# esp32-poe-thermocouple-hat-prod-onboard.net
KiCad netlist of a schematic drawn in EAGLE
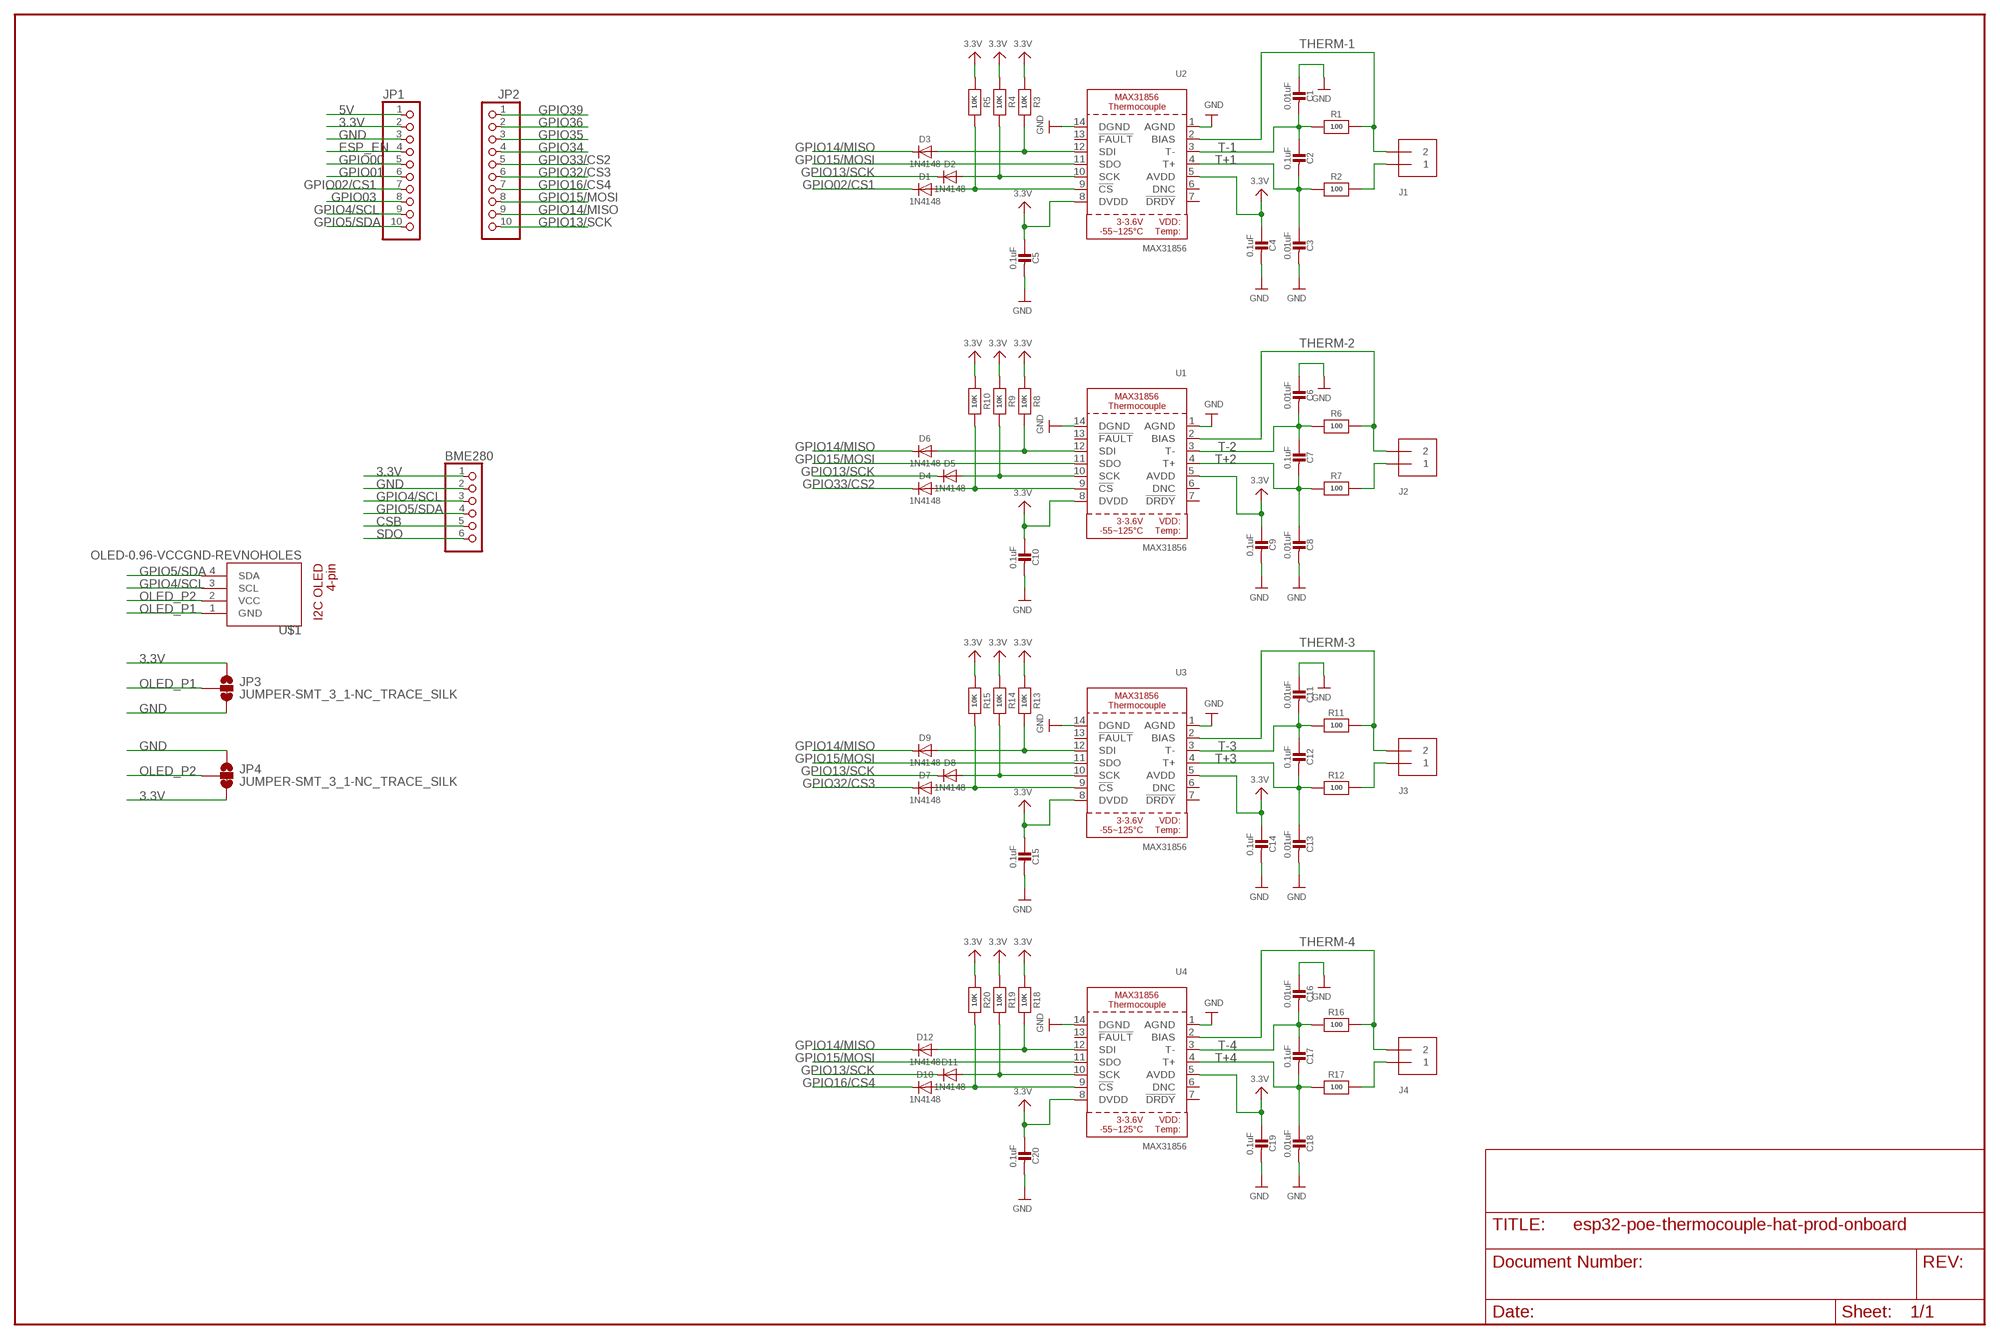
[diagram p0: schematic, sheet 1]

(export (version "E")
  (design (tool "Eeschema 10.0.6"))
  (components
    (comp (ref "BME280")
      (value "PINHD-1X6")
      (footprint "eagle-import:1X06")
      (libsource (lib "eagle-import") (part "PINHD-1X6"))
    )
    (comp (ref "C1")
      (value "0.01uF")
      (footprint "eagle-import:0805_10MGAP")
      (libsource (lib "eagle-import") (part "CAP_CERAMIC0805_10MGAP"))
    )
    (comp (ref "C2")
      (value "0.1uF")
      (footprint "eagle-import:0805-NO")
      (libsource (lib "eagle-import") (part "CAP_CERAMIC0805-NOOUTLINE"))
    )
    (comp (ref "C3")
      (value "0.01uF")
      (footprint "eagle-import:0805-NO")
      (libsource (lib "eagle-import") (part "CAP_CERAMIC0805-NOOUTLINE"))
    )
    (comp (ref "C4")
      (value "0.1uF")
      (footprint "eagle-import:0805-NO")
      (libsource (lib "eagle-import") (part "CAP_CERAMIC0805-NOOUTLINE"))
    )
    (comp (ref "C5")
      (value "0.1uF")
      (footprint "eagle-import:0805-NO")
      (libsource (lib "eagle-import") (part "CAP_CERAMIC0805-NOOUTLINE"))
    )
    (comp (ref "C6")
      (value "0.01uF")
      (footprint "eagle-import:0805_10MGAP")
      (libsource (lib "eagle-import") (part "CAP_CERAMIC0805_10MGAP"))
    )
    (comp (ref "C7")
      (value "0.1uF")
      (footprint "eagle-import:0805-NO")
      (libsource (lib "eagle-import") (part "CAP_CERAMIC0805-NOOUTLINE"))
    )
    (comp (ref "C8")
      (value "0.01uF")
      (footprint "eagle-import:0805-NO")
      (libsource (lib "eagle-import") (part "CAP_CERAMIC0805-NOOUTLINE"))
    )
    (comp (ref "C9")
      (value "0.1uF")
      (footprint "eagle-import:0805-NO")
      (libsource (lib "eagle-import") (part "CAP_CERAMIC0805-NOOUTLINE"))
    )
    (comp (ref "C10")
      (value "0.1uF")
      (footprint "eagle-import:0805-NO")
      (libsource (lib "eagle-import") (part "CAP_CERAMIC0805-NOOUTLINE"))
    )
    (comp (ref "C11")
      (value "0.01uF")
      (footprint "eagle-import:0805_10MGAP")
      (libsource (lib "eagle-import") (part "CAP_CERAMIC0805_10MGAP"))
    )
    (comp (ref "C12")
      (value "0.1uF")
      (footprint "eagle-import:0805-NO")
      (libsource (lib "eagle-import") (part "CAP_CERAMIC0805-NOOUTLINE"))
    )
    (comp (ref "C13")
      (value "0.01uF")
      (footprint "eagle-import:0805-NO")
      (libsource (lib "eagle-import") (part "CAP_CERAMIC0805-NOOUTLINE"))
    )
    (comp (ref "C14")
      (value "0.1uF")
      (footprint "eagle-import:0805-NO")
      (libsource (lib "eagle-import") (part "CAP_CERAMIC0805-NOOUTLINE"))
    )
    (comp (ref "C15")
      (value "0.1uF")
      (footprint "eagle-import:0805-NO")
      (libsource (lib "eagle-import") (part "CAP_CERAMIC0805-NOOUTLINE"))
    )
    (comp (ref "C16")
      (value "0.01uF")
      (footprint "eagle-import:0805_10MGAP")
      (libsource (lib "eagle-import") (part "CAP_CERAMIC0805_10MGAP"))
    )
    (comp (ref "C17")
      (value "0.1uF")
      (footprint "eagle-import:0805-NO")
      (libsource (lib "eagle-import") (part "CAP_CERAMIC0805-NOOUTLINE"))
    )
    (comp (ref "C18")
      (value "0.01uF")
      (footprint "eagle-import:0805-NO")
      (libsource (lib "eagle-import") (part "CAP_CERAMIC0805-NOOUTLINE"))
    )
    (comp (ref "C19")
      (value "0.1uF")
      (footprint "eagle-import:0805-NO")
      (libsource (lib "eagle-import") (part "CAP_CERAMIC0805-NOOUTLINE"))
    )
    (comp (ref "C20")
      (value "0.1uF")
      (footprint "eagle-import:0805-NO")
      (libsource (lib "eagle-import") (part "CAP_CERAMIC0805-NOOUTLINE"))
    )
    (comp (ref "D1")
      (value "1N4148")
      (footprint "eagle-import:SOD-323")
      (libsource (lib "eagle-import") (part "DIODESOD-323"))
    )
    (comp (ref "D2")
      (value "1N4148")
      (footprint "eagle-import:SOD-323")
      (libsource (lib "eagle-import") (part "DIODESOD-323"))
    )
    (comp (ref "D3")
      (value "1N4148")
      (footprint "eagle-import:SOD-323")
      (libsource (lib "eagle-import") (part "DIODESOD-323"))
    )
    (comp (ref "D4")
      (value "1N4148")
      (footprint "eagle-import:SOD-323")
      (libsource (lib "eagle-import") (part "DIODESOD-323"))
    )
    (comp (ref "D5")
      (value "1N4148")
      (footprint "eagle-import:SOD-323")
      (libsource (lib "eagle-import") (part "DIODESOD-323"))
    )
    (comp (ref "D6")
      (value "1N4148")
      (footprint "eagle-import:SOD-323")
      (libsource (lib "eagle-import") (part "DIODESOD-323"))
    )
    (comp (ref "D7")
      (value "1N4148")
      (footprint "eagle-import:SOD-323")
      (libsource (lib "eagle-import") (part "DIODESOD-323"))
    )
    (comp (ref "D8")
      (value "1N4148")
      (footprint "eagle-import:SOD-323")
      (libsource (lib "eagle-import") (part "DIODESOD-323"))
    )
    (comp (ref "D9")
      (value "1N4148")
      (footprint "eagle-import:SOD-323")
      (libsource (lib "eagle-import") (part "DIODESOD-323"))
    )
    (comp (ref "D10")
      (value "1N4148")
      (footprint "eagle-import:SOD-323")
      (libsource (lib "eagle-import") (part "DIODESOD-323"))
    )
    (comp (ref "D11")
      (value "1N4148")
      (footprint "eagle-import:SOD-323")
      (libsource (lib "eagle-import") (part "DIODESOD-323"))
    )
    (comp (ref "D12")
      (value "1N4148")
      (footprint "eagle-import:SOD-323")
      (libsource (lib "eagle-import") (part "DIODESOD-323"))
    )
    (comp (ref "J1")
      (value "TERMBLOCK_1X2-7.62-SCREW")
      (footprint "eagle-import:TERMBLOCK_1X2-7.62MM-SCREW")
      (libsource (lib "eagle-import") (part "TERMBLOCK_1X2-7.62-SCREW"))
    )
    (comp (ref "J2")
      (value "TERMBLOCK_1X2-7.62-SCREW")
      (footprint "eagle-import:TERMBLOCK_1X2-7.62MM-SCREW")
      (libsource (lib "eagle-import") (part "TERMBLOCK_1X2-7.62-SCREW"))
    )
    (comp (ref "J3")
      (value "TERMBLOCK_1X2-7.62-SCREW")
      (footprint "eagle-import:TERMBLOCK_1X2-7.62MM-SCREW")
      (libsource (lib "eagle-import") (part "TERMBLOCK_1X2-7.62-SCREW"))
    )
    (comp (ref "J4")
      (value "TERMBLOCK_1X2-7.62-SCREW")
      (footprint "eagle-import:TERMBLOCK_1X2-7.62MM-SCREW")
      (libsource (lib "eagle-import") (part "TERMBLOCK_1X2-7.62-SCREW"))
    )
    (comp (ref "JP1")
      (value "PINHD-1X10")
      (footprint "eagle-import:1X10")
      (libsource (lib "eagle-import") (part "PINHD-1X10"))
    )
    (comp (ref "JP2")
      (value "PINHD-1X10")
      (footprint "eagle-import:1X10")
      (libsource (lib "eagle-import") (part "PINHD-1X10"))
    )
    (comp (ref "JP3")
      (value "JUMPER-SMT_3_1-NC_TRACE_SILK")
      (footprint "eagle-import:SMT-JUMPER_3_1-NC_TRACE_SILK")
      (libsource (lib "eagle-import") (part "JUMPER-SMT_3_1-NC_TRACE_SILK"))
    )
    (comp (ref "JP4")
      (value "JUMPER-SMT_3_1-NC_TRACE_SILK")
      (footprint "eagle-import:SMT-JUMPER_3_1-NC_TRACE_SILK")
      (libsource (lib "eagle-import") (part "JUMPER-SMT_3_1-NC_TRACE_SILK"))
    )
    (comp (ref "R1")
      (value "100")
      (footprint "eagle-import:0805-NO")
      (libsource (lib "eagle-import") (part "RESISTOR0805_NOOUTLINE"))
    )
    (comp (ref "R2")
      (value "100")
      (footprint "eagle-import:0805-NO")
      (libsource (lib "eagle-import") (part "RESISTOR0805_NOOUTLINE"))
    )
    (comp (ref "R3")
      (value "10K")
      (footprint "eagle-import:0805-NO")
      (libsource (lib "eagle-import") (part "RESISTOR0805_NOOUTLINE"))
    )
    (comp (ref "R4")
      (value "10K")
      (footprint "eagle-import:0805-NO")
      (libsource (lib "eagle-import") (part "RESISTOR0805_NOOUTLINE"))
    )
    (comp (ref "R5")
      (value "10K")
      (footprint "eagle-import:0805-NO")
      (libsource (lib "eagle-import") (part "RESISTOR0805_NOOUTLINE"))
    )
    (comp (ref "R6")
      (value "100")
      (footprint "eagle-import:0805-NO")
      (libsource (lib "eagle-import") (part "RESISTOR0805_NOOUTLINE"))
    )
    (comp (ref "R7")
      (value "100")
      (footprint "eagle-import:0805-NO")
      (libsource (lib "eagle-import") (part "RESISTOR0805_NOOUTLINE"))
    )
    (comp (ref "R8")
      (value "10K")
      (footprint "eagle-import:0805-NO")
      (libsource (lib "eagle-import") (part "RESISTOR0805_NOOUTLINE"))
    )
    (comp (ref "R9")
      (value "10K")
      (footprint "eagle-import:0805-NO")
      (libsource (lib "eagle-import") (part "RESISTOR0805_NOOUTLINE"))
    )
    (comp (ref "R10")
      (value "10K")
      (footprint "eagle-import:0805-NO")
      (libsource (lib "eagle-import") (part "RESISTOR0805_NOOUTLINE"))
    )
    (comp (ref "R11")
      (value "100")
      (footprint "eagle-import:0805-NO")
      (libsource (lib "eagle-import") (part "RESISTOR0805_NOOUTLINE"))
    )
    (comp (ref "R12")
      (value "100")
      (footprint "eagle-import:0805-NO")
      (libsource (lib "eagle-import") (part "RESISTOR0805_NOOUTLINE"))
    )
    (comp (ref "R13")
      (value "10K")
      (footprint "eagle-import:0805-NO")
      (libsource (lib "eagle-import") (part "RESISTOR0805_NOOUTLINE"))
    )
    (comp (ref "R14")
      (value "10K")
      (footprint "eagle-import:0805-NO")
      (libsource (lib "eagle-import") (part "RESISTOR0805_NOOUTLINE"))
    )
    (comp (ref "R15")
      (value "10K")
      (footprint "eagle-import:0805-NO")
      (libsource (lib "eagle-import") (part "RESISTOR0805_NOOUTLINE"))
    )
    (comp (ref "R16")
      (value "100")
      (footprint "eagle-import:0805-NO")
      (libsource (lib "eagle-import") (part "RESISTOR0805_NOOUTLINE"))
    )
    (comp (ref "R17")
      (value "100")
      (footprint "eagle-import:0805-NO")
      (libsource (lib "eagle-import") (part "RESISTOR0805_NOOUTLINE"))
    )
    (comp (ref "R18")
      (value "10K")
      (footprint "eagle-import:0805-NO")
      (libsource (lib "eagle-import") (part "RESISTOR0805_NOOUTLINE"))
    )
    (comp (ref "R19")
      (value "10K")
      (footprint "eagle-import:0805-NO")
      (libsource (lib "eagle-import") (part "RESISTOR0805_NOOUTLINE"))
    )
    (comp (ref "R20")
      (value "10K")
      (footprint "eagle-import:0805-NO")
      (libsource (lib "eagle-import") (part "RESISTOR0805_NOOUTLINE"))
    )
    (comp (ref "U$1")
      (value "OLED-0.96-VCCGND-REVNOHOLES")
      (footprint "eagle-import:OLED-I2C-4PIN-NOHOLES")
      (libsource (lib "eagle-import") (part "OLED-0.96-VCCGND-REVNOHOLES"))
    )
    (comp (ref "U1")
      (value "MAX31856")
      (footprint "eagle-import:TSSOP14")
      (libsource (lib "eagle-import") (part "MAX31856"))
    )
    (comp (ref "U2")
      (value "MAX31856")
      (footprint "eagle-import:TSSOP14")
      (libsource (lib "eagle-import") (part "MAX31856"))
    )
    (comp (ref "U3")
      (value "MAX31856")
      (footprint "eagle-import:TSSOP14")
      (libsource (lib "eagle-import") (part "MAX31856"))
    )
    (comp (ref "U4")
      (value "MAX31856")
      (footprint "eagle-import:TSSOP14")
      (libsource (lib "eagle-import") (part "MAX31856"))
    )
  )
  (nets
    (net (code "1") (name "/5V") (class "Default")
      (node (ref "JP1") (pin "1") (pinfunction "1_1") (pintype "passive"))
    )
    (net (code "2") (name "/CSB") (class "Default")
      (node (ref "BME280") (pin "5") (pinfunction "5_5") (pintype "passive"))
    )
    (net (code "3") (name "/ESP_EN") (class "Default")
      (node (ref "JP1") (pin "4") (pinfunction "4_4") (pintype "passive"))
    )
    (net (code "4") (name "/GPIO00") (class "Default")
      (node (ref "JP1") (pin "5") (pinfunction "5_5") (pintype "passive"))
    )
    (net (code "5") (name "/GPIO01") (class "Default")
      (node (ref "JP1") (pin "6") (pinfunction "6_6") (pintype "passive"))
    )
    (net (code "6") (name "/GPIO02{slash}CS1") (class "Default")
      (node (ref "D1") (pin "C") (pinfunction "C_C") (pintype "passive"))
      (node (ref "JP1") (pin "7") (pinfunction "7_7") (pintype "passive"))
    )
    (net (code "7") (name "/GPIO03") (class "Default")
      (node (ref "JP1") (pin "8") (pinfunction "8_8") (pintype "passive"))
    )
    (net (code "8") (name "/GPIO4{slash}SCL") (class "Default")
      (node (ref "BME280") (pin "3") (pinfunction "3_3") (pintype "passive"))
      (node (ref "JP1") (pin "9") (pinfunction "9_9") (pintype "passive"))
      (node (ref "U$1") (pin "3") (pinfunction "SCL_3") (pintype "bidirectional"))
    )
    (net (code "9") (name "/GPIO5{slash}SDA") (class "Default")
      (node (ref "BME280") (pin "4") (pinfunction "4_4") (pintype "passive"))
      (node (ref "JP1") (pin "10") (pinfunction "10_10") (pintype "passive"))
      (node (ref "U$1") (pin "4") (pinfunction "SDA_4") (pintype "bidirectional"))
    )
    (net (code "10") (name "/GPIO13{slash}SCK") (class "Default")
      (node (ref "D11") (pin "C") (pinfunction "C_C") (pintype "passive"))
      (node (ref "D2") (pin "C") (pinfunction "C_C") (pintype "passive"))
      (node (ref "D5") (pin "C") (pinfunction "C_C") (pintype "passive"))
      (node (ref "D8") (pin "C") (pinfunction "C_C") (pintype "passive"))
      (node (ref "JP2") (pin "10") (pinfunction "10_10") (pintype "passive"))
    )
    (net (code "11") (name "/GPIO14{slash}MISO") (class "Default")
      (node (ref "D12") (pin "C") (pinfunction "C_C") (pintype "passive"))
      (node (ref "D3") (pin "C") (pinfunction "C_C") (pintype "passive"))
      (node (ref "D6") (pin "C") (pinfunction "C_C") (pintype "passive"))
      (node (ref "D9") (pin "C") (pinfunction "C_C") (pintype "passive"))
      (node (ref "JP2") (pin "9") (pinfunction "9_9") (pintype "passive"))
    )
    (net (code "12") (name "/GPIO15{slash}MOSI") (class "Default")
      (node (ref "JP2") (pin "8") (pinfunction "8_8") (pintype "passive"))
      (node (ref "U1") (pin "11") (pinfunction "SDO_11") (pintype "output"))
      (node (ref "U2") (pin "11") (pinfunction "SDO_11") (pintype "output"))
      (node (ref "U3") (pin "11") (pinfunction "SDO_11") (pintype "output"))
      (node (ref "U4") (pin "11") (pinfunction "SDO_11") (pintype "output"))
    )
    (net (code "13") (name "/GPIO16{slash}CS4") (class "Default")
      (node (ref "D10") (pin "C") (pinfunction "C_C") (pintype "passive"))
      (node (ref "JP2") (pin "7") (pinfunction "7_7") (pintype "passive"))
    )
    (net (code "14") (name "/GPIO32{slash}CS3") (class "Default")
      (node (ref "D7") (pin "C") (pinfunction "C_C") (pintype "passive"))
      (node (ref "JP2") (pin "6") (pinfunction "6_6") (pintype "passive"))
    )
    (net (code "15") (name "/GPIO33{slash}CS2") (class "Default")
      (node (ref "D4") (pin "C") (pinfunction "C_C") (pintype "passive"))
      (node (ref "JP2") (pin "5") (pinfunction "5_5") (pintype "passive"))
    )
    (net (code "16") (name "/GPIO34") (class "Default")
      (node (ref "JP2") (pin "4") (pinfunction "4_4") (pintype "passive"))
    )
    (net (code "17") (name "/GPIO35") (class "Default")
      (node (ref "JP2") (pin "3") (pinfunction "3_3") (pintype "passive"))
    )
    (net (code "18") (name "/GPIO36") (class "Default")
      (node (ref "JP2") (pin "2") (pinfunction "2_2") (pintype "passive"))
    )
    (net (code "19") (name "/GPIO39") (class "Default")
      (node (ref "JP2") (pin "1") (pinfunction "1_1") (pintype "passive"))
    )
    (net (code "20") (name "/OLED_P1") (class "Default")
      (node (ref "JP3") (pin "2") (pinfunction "2_2") (pintype "passive"))
      (node (ref "U$1") (pin "1") (pinfunction "GND_1") (pintype "bidirectional"))
    )
    (net (code "21") (name "/OLED_P2") (class "Default")
      (node (ref "JP4") (pin "2") (pinfunction "2_2") (pintype "passive"))
      (node (ref "U$1") (pin "2") (pinfunction "VCC_2") (pintype "bidirectional"))
    )
    (net (code "22") (name "/SDO") (class "Default")
      (node (ref "BME280") (pin "6") (pinfunction "6_6") (pintype "passive"))
    )
    (net (code "23") (name "/T+1") (class "Default")
      (node (ref "C2") (pin "2") (pinfunction "2_2") (pintype "passive"))
      (node (ref "C3") (pin "1") (pinfunction "1_1") (pintype "passive"))
      (node (ref "R2") (pin "2") (pinfunction "2_2") (pintype "passive"))
      (node (ref "U2") (pin "4") (pinfunction "T+_4") (pintype "input"))
    )
    (net (code "24") (name "/T+2") (class "Default")
      (node (ref "C7") (pin "2") (pinfunction "2_2") (pintype "passive"))
      (node (ref "C8") (pin "1") (pinfunction "1_1") (pintype "passive"))
      (node (ref "R7") (pin "2") (pinfunction "2_2") (pintype "passive"))
      (node (ref "U1") (pin "4") (pinfunction "T+_4") (pintype "input"))
    )
    (net (code "25") (name "/T+3") (class "Default")
      (node (ref "C12") (pin "2") (pinfunction "2_2") (pintype "passive"))
      (node (ref "C13") (pin "1") (pinfunction "1_1") (pintype "passive"))
      (node (ref "R12") (pin "2") (pinfunction "2_2") (pintype "passive"))
      (node (ref "U3") (pin "4") (pinfunction "T+_4") (pintype "input"))
    )
    (net (code "26") (name "/T+4") (class "Default")
      (node (ref "C17") (pin "2") (pinfunction "2_2") (pintype "passive"))
      (node (ref "C18") (pin "1") (pinfunction "1_1") (pintype "passive"))
      (node (ref "R17") (pin "2") (pinfunction "2_2") (pintype "passive"))
      (node (ref "U4") (pin "4") (pinfunction "T+_4") (pintype "input"))
    )
    (net (code "27") (name "/T-1") (class "Default")
      (node (ref "C1") (pin "2") (pinfunction "2_2") (pintype "passive"))
      (node (ref "C2") (pin "1") (pinfunction "1_1") (pintype "passive"))
      (node (ref "R1") (pin "2") (pinfunction "2_2") (pintype "passive"))
      (node (ref "U2") (pin "3") (pinfunction "T-_3") (pintype "input"))
    )
    (net (code "28") (name "/T-2") (class "Default")
      (node (ref "C6") (pin "2") (pinfunction "2_2") (pintype "passive"))
      (node (ref "C7") (pin "1") (pinfunction "1_1") (pintype "passive"))
      (node (ref "R6") (pin "2") (pinfunction "2_2") (pintype "passive"))
      (node (ref "U1") (pin "3") (pinfunction "T-_3") (pintype "input"))
    )
    (net (code "29") (name "/T-3") (class "Default")
      (node (ref "C11") (pin "2") (pinfunction "2_2") (pintype "passive"))
      (node (ref "C12") (pin "1") (pinfunction "1_1") (pintype "passive"))
      (node (ref "R11") (pin "2") (pinfunction "2_2") (pintype "passive"))
      (node (ref "U3") (pin "3") (pinfunction "T-_3") (pintype "input"))
    )
    (net (code "30") (name "/T-4") (class "Default")
      (node (ref "C16") (pin "2") (pinfunction "2_2") (pintype "passive"))
      (node (ref "C17") (pin "1") (pinfunction "1_1") (pintype "passive"))
      (node (ref "R16") (pin "2") (pinfunction "2_2") (pintype "passive"))
      (node (ref "U4") (pin "3") (pinfunction "T-_3") (pintype "input"))
    )
    (net (code "31") (name "/THERM-1") (class "Default")
      (node (ref "J1") (pin "2") (pinfunction "2_2") (pintype "passive"))
      (node (ref "R1") (pin "1") (pinfunction "1_1") (pintype "passive"))
      (node (ref "U2") (pin "2") (pinfunction "BIAS_2") (pintype "power_in"))
    )
    (net (code "32") (name "/THERM-2") (class "Default")
      (node (ref "J2") (pin "2") (pinfunction "2_2") (pintype "passive"))
      (node (ref "R6") (pin "1") (pinfunction "1_1") (pintype "passive"))
      (node (ref "U1") (pin "2") (pinfunction "BIAS_2") (pintype "power_in"))
    )
    (net (code "33") (name "/THERM-3") (class "Default")
      (node (ref "J3") (pin "2") (pinfunction "2_2") (pintype "passive"))
      (node (ref "R11") (pin "1") (pinfunction "1_1") (pintype "passive"))
      (node (ref "U3") (pin "2") (pinfunction "BIAS_2") (pintype "power_in"))
    )
    (net (code "34") (name "/THERM-4") (class "Default")
      (node (ref "J4") (pin "2") (pinfunction "2_2") (pintype "passive"))
      (node (ref "R16") (pin "1") (pinfunction "1_1") (pintype "passive"))
      (node (ref "U4") (pin "2") (pinfunction "BIAS_2") (pintype "power_in"))
    )
    (net (code "35") (name "3.3V") (class "Default")
      (node (ref "BME280") (pin "1") (pinfunction "1_1") (pintype "passive"))
      (node (ref "C10") (pin "1") (pinfunction "1_1") (pintype "passive"))
      (node (ref "C14") (pin "1") (pinfunction "1_1") (pintype "passive"))
      (node (ref "C15") (pin "1") (pinfunction "1_1") (pintype "passive"))
      (node (ref "C19") (pin "1") (pinfunction "1_1") (pintype "passive"))
      (node (ref "C20") (pin "1") (pinfunction "1_1") (pintype "passive"))
      (node (ref "C4") (pin "1") (pinfunction "1_1") (pintype "passive"))
      (node (ref "C5") (pin "1") (pinfunction "1_1") (pintype "passive"))
      (node (ref "C9") (pin "1") (pinfunction "1_1") (pintype "passive"))
      (node (ref "JP1") (pin "2") (pinfunction "2_2") (pintype "passive"))
      (node (ref "JP3") (pin "1") (pinfunction "1_1") (pintype "passive"))
      (node (ref "JP4") (pin "3") (pinfunction "3_3") (pintype "passive"))
      (node (ref "R10") (pin "2") (pinfunction "2_2") (pintype "passive"))
      (node (ref "R13") (pin "2") (pinfunction "2_2") (pintype "passive"))
      (node (ref "R14") (pin "2") (pinfunction "2_2") (pintype "passive"))
      (node (ref "R15") (pin "2") (pinfunction "2_2") (pintype "passive"))
      (node (ref "R18") (pin "2") (pinfunction "2_2") (pintype "passive"))
      (node (ref "R19") (pin "2") (pinfunction "2_2") (pintype "passive"))
      (node (ref "R20") (pin "2") (pinfunction "2_2") (pintype "passive"))
      (node (ref "R3") (pin "2") (pinfunction "2_2") (pintype "passive"))
      (node (ref "R4") (pin "2") (pinfunction "2_2") (pintype "passive"))
      (node (ref "R5") (pin "2") (pinfunction "2_2") (pintype "passive"))
      (node (ref "R8") (pin "2") (pinfunction "2_2") (pintype "passive"))
      (node (ref "R9") (pin "2") (pinfunction "2_2") (pintype "passive"))
      (node (ref "U1") (pin "5") (pinfunction "AVDD_5") (pintype "power_in"))
      (node (ref "U1") (pin "8") (pinfunction "DVDD_8") (pintype "power_in"))
      (node (ref "U2") (pin "5") (pinfunction "AVDD_5") (pintype "power_in"))
      (node (ref "U2") (pin "8") (pinfunction "DVDD_8") (pintype "power_in"))
      (node (ref "U3") (pin "5") (pinfunction "AVDD_5") (pintype "power_in"))
      (node (ref "U3") (pin "8") (pinfunction "DVDD_8") (pintype "power_in"))
      (node (ref "U4") (pin "5") (pinfunction "AVDD_5") (pintype "power_in"))
      (node (ref "U4") (pin "8") (pinfunction "DVDD_8") (pintype "power_in"))
    )
    (net (code "36") (name "GND") (class "Default")
      (node (ref "BME280") (pin "2") (pinfunction "2_2") (pintype "passive"))
      (node (ref "C1") (pin "1") (pinfunction "1_1") (pintype "passive"))
      (node (ref "C10") (pin "2") (pinfunction "2_2") (pintype "passive"))
      (node (ref "C11") (pin "1") (pinfunction "1_1") (pintype "passive"))
      (node (ref "C13") (pin "2") (pinfunction "2_2") (pintype "passive"))
      (node (ref "C14") (pin "2") (pinfunction "2_2") (pintype "passive"))
      (node (ref "C15") (pin "2") (pinfunction "2_2") (pintype "passive"))
      (node (ref "C16") (pin "1") (pinfunction "1_1") (pintype "passive"))
      (node (ref "C18") (pin "2") (pinfunction "2_2") (pintype "passive"))
      (node (ref "C19") (pin "2") (pinfunction "2_2") (pintype "passive"))
      (node (ref "C20") (pin "2") (pinfunction "2_2") (pintype "passive"))
      (node (ref "C3") (pin "2") (pinfunction "2_2") (pintype "passive"))
      (node (ref "C4") (pin "2") (pinfunction "2_2") (pintype "passive"))
      (node (ref "C5") (pin "2") (pinfunction "2_2") (pintype "passive"))
      (node (ref "C6") (pin "1") (pinfunction "1_1") (pintype "passive"))
      (node (ref "C8") (pin "2") (pinfunction "2_2") (pintype "passive"))
      (node (ref "C9") (pin "2") (pinfunction "2_2") (pintype "passive"))
      (node (ref "JP1") (pin "3") (pinfunction "3_3") (pintype "passive"))
      (node (ref "JP3") (pin "3") (pinfunction "3_3") (pintype "passive"))
      (node (ref "JP4") (pin "1") (pinfunction "1_1") (pintype "passive"))
      (node (ref "U1") (pin "1") (pinfunction "AGND_1") (pintype "power_in"))
      (node (ref "U1") (pin "14") (pinfunction "DGND_14") (pintype "power_in"))
      (node (ref "U2") (pin "1") (pinfunction "AGND_1") (pintype "power_in"))
      (node (ref "U2") (pin "14") (pinfunction "DGND_14") (pintype "power_in"))
      (node (ref "U3") (pin "1") (pinfunction "AGND_1") (pintype "power_in"))
      (node (ref "U3") (pin "14") (pinfunction "DGND_14") (pintype "power_in"))
      (node (ref "U4") (pin "1") (pinfunction "AGND_1") (pintype "power_in"))
      (node (ref "U4") (pin "14") (pinfunction "DGND_14") (pintype "power_in"))
    )
    (net (code "37") (name "Net-(J1-Pad1)") (class "Default")
      (node (ref "J1") (pin "1") (pinfunction "1_1") (pintype "passive"))
      (node (ref "R2") (pin "1") (pinfunction "1_1") (pintype "passive"))
    )
    (net (code "38") (name "Net-(J2-Pad1)") (class "Default")
      (node (ref "J2") (pin "1") (pinfunction "1_1") (pintype "passive"))
      (node (ref "R7") (pin "1") (pinfunction "1_1") (pintype "passive"))
    )
    (net (code "39") (name "Net-(J3-Pad1)") (class "Default")
      (node (ref "J3") (pin "1") (pinfunction "1_1") (pintype "passive"))
      (node (ref "R12") (pin "1") (pinfunction "1_1") (pintype "passive"))
    )
    (net (code "40") (name "Net-(J4-Pad1)") (class "Default")
      (node (ref "J4") (pin "1") (pinfunction "1_1") (pintype "passive"))
      (node (ref "R17") (pin "1") (pinfunction "1_1") (pintype "passive"))
    )
    (net (code "41") (name "Net-(U1-SCK)") (class "Default")
      (node (ref "D5") (pin "A") (pinfunction "A_A") (pintype "passive"))
      (node (ref "R9") (pin "1") (pinfunction "1_1") (pintype "passive"))
      (node (ref "U1") (pin "10") (pinfunction "SCK_10") (pintype "input"))
    )
    (net (code "42") (name "Net-(U1-SDI)") (class "Default")
      (node (ref "D6") (pin "A") (pinfunction "A_A") (pintype "passive"))
      (node (ref "R8") (pin "1") (pinfunction "1_1") (pintype "passive"))
      (node (ref "U1") (pin "12") (pinfunction "SDI_12") (pintype "input"))
    )
    (net (code "43") (name "Net-(U1-~{CS})") (class "Default")
      (node (ref "D4") (pin "A") (pinfunction "A_A") (pintype "passive"))
      (node (ref "R10") (pin "1") (pinfunction "1_1") (pintype "passive"))
      (node (ref "U1") (pin "9") (pinfunction "~{CS}_9") (pintype "input"))
    )
    (net (code "44") (name "Net-(U2-SCK)") (class "Default")
      (node (ref "D2") (pin "A") (pinfunction "A_A") (pintype "passive"))
      (node (ref "R4") (pin "1") (pinfunction "1_1") (pintype "passive"))
      (node (ref "U2") (pin "10") (pinfunction "SCK_10") (pintype "input"))
    )
    (net (code "45") (name "Net-(U2-SDI)") (class "Default")
      (node (ref "D3") (pin "A") (pinfunction "A_A") (pintype "passive"))
      (node (ref "R3") (pin "1") (pinfunction "1_1") (pintype "passive"))
      (node (ref "U2") (pin "12") (pinfunction "SDI_12") (pintype "input"))
    )
    (net (code "46") (name "Net-(U2-~{CS})") (class "Default")
      (node (ref "D1") (pin "A") (pinfunction "A_A") (pintype "passive"))
      (node (ref "R5") (pin "1") (pinfunction "1_1") (pintype "passive"))
      (node (ref "U2") (pin "9") (pinfunction "~{CS}_9") (pintype "input"))
    )
    (net (code "47") (name "Net-(U3-SCK)") (class "Default")
      (node (ref "D8") (pin "A") (pinfunction "A_A") (pintype "passive"))
      (node (ref "R14") (pin "1") (pinfunction "1_1") (pintype "passive"))
      (node (ref "U3") (pin "10") (pinfunction "SCK_10") (pintype "input"))
    )
    (net (code "48") (name "Net-(U3-SDI)") (class "Default")
      (node (ref "D9") (pin "A") (pinfunction "A_A") (pintype "passive"))
      (node (ref "R13") (pin "1") (pinfunction "1_1") (pintype "passive"))
      (node (ref "U3") (pin "12") (pinfunction "SDI_12") (pintype "input"))
    )
    (net (code "49") (name "Net-(U3-~{CS})") (class "Default")
      (node (ref "D7") (pin "A") (pinfunction "A_A") (pintype "passive"))
      (node (ref "R15") (pin "1") (pinfunction "1_1") (pintype "passive"))
      (node (ref "U3") (pin "9") (pinfunction "~{CS}_9") (pintype "input"))
    )
    (net (code "50") (name "Net-(U4-SCK)") (class "Default")
      (node (ref "D11") (pin "A") (pinfunction "A_A") (pintype "passive"))
      (node (ref "R19") (pin "1") (pinfunction "1_1") (pintype "passive"))
      (node (ref "U4") (pin "10") (pinfunction "SCK_10") (pintype "input"))
    )
    (net (code "51") (name "Net-(U4-SDI)") (class "Default")
      (node (ref "D12") (pin "A") (pinfunction "A_A") (pintype "passive"))
      (node (ref "R18") (pin "1") (pinfunction "1_1") (pintype "passive"))
      (node (ref "U4") (pin "12") (pinfunction "SDI_12") (pintype "input"))
    )
    (net (code "52") (name "Net-(U4-~{CS})") (class "Default")
      (node (ref "D10") (pin "A") (pinfunction "A_A") (pintype "passive"))
      (node (ref "R20") (pin "1") (pinfunction "1_1") (pintype "passive"))
      (node (ref "U4") (pin "9") (pinfunction "~{CS}_9") (pintype "input"))
    )
    (net (code "53") (name "unconnected-(U1-DNC-Pad6)") (class "Default")
      (node (ref "U1") (pin "6") (pinfunction "DNC_6") (pintype "no_connect"))
    )
    (net (code "54") (name "unconnected-(U1-~{DRDY}-Pad7)") (class "Default")
      (node (ref "U1") (pin "7") (pinfunction "~{DRDY}_7") (pintype "output"))
    )
    (net (code "55") (name "unconnected-(U1-~{FAULT}-Pad13)") (class "Default")
      (node (ref "U1") (pin "13") (pinfunction "~{FAULT}_13") (pintype "output"))
    )
    (net (code "56") (name "unconnected-(U2-DNC-Pad6)") (class "Default")
      (node (ref "U2") (pin "6") (pinfunction "DNC_6") (pintype "no_connect"))
    )
    (net (code "57") (name "unconnected-(U2-~{DRDY}-Pad7)") (class "Default")
      (node (ref "U2") (pin "7") (pinfunction "~{DRDY}_7") (pintype "output"))
    )
    (net (code "58") (name "unconnected-(U2-~{FAULT}-Pad13)") (class "Default")
      (node (ref "U2") (pin "13") (pinfunction "~{FAULT}_13") (pintype "output"))
    )
    (net (code "59") (name "unconnected-(U3-DNC-Pad6)") (class "Default")
      (node (ref "U3") (pin "6") (pinfunction "DNC_6") (pintype "no_connect"))
    )
    (net (code "60") (name "unconnected-(U3-~{DRDY}-Pad7)") (class "Default")
      (node (ref "U3") (pin "7") (pinfunction "~{DRDY}_7") (pintype "output"))
    )
    (net (code "61") (name "unconnected-(U3-~{FAULT}-Pad13)") (class "Default")
      (node (ref "U3") (pin "13") (pinfunction "~{FAULT}_13") (pintype "output"))
    )
    (net (code "62") (name "unconnected-(U4-DNC-Pad6)") (class "Default")
      (node (ref "U4") (pin "6") (pinfunction "DNC_6") (pintype "no_connect"))
    )
    (net (code "63") (name "unconnected-(U4-~{DRDY}-Pad7)") (class "Default")
      (node (ref "U4") (pin "7") (pinfunction "~{DRDY}_7") (pintype "output"))
    )
    (net (code "64") (name "unconnected-(U4-~{FAULT}-Pad13)") (class "Default")
      (node (ref "U4") (pin "13") (pinfunction "~{FAULT}_13") (pintype "output"))
    )
  )
)
